# olm-flora-sqw-long.net
KiCad netlist of a schematic drawn in EAGLE
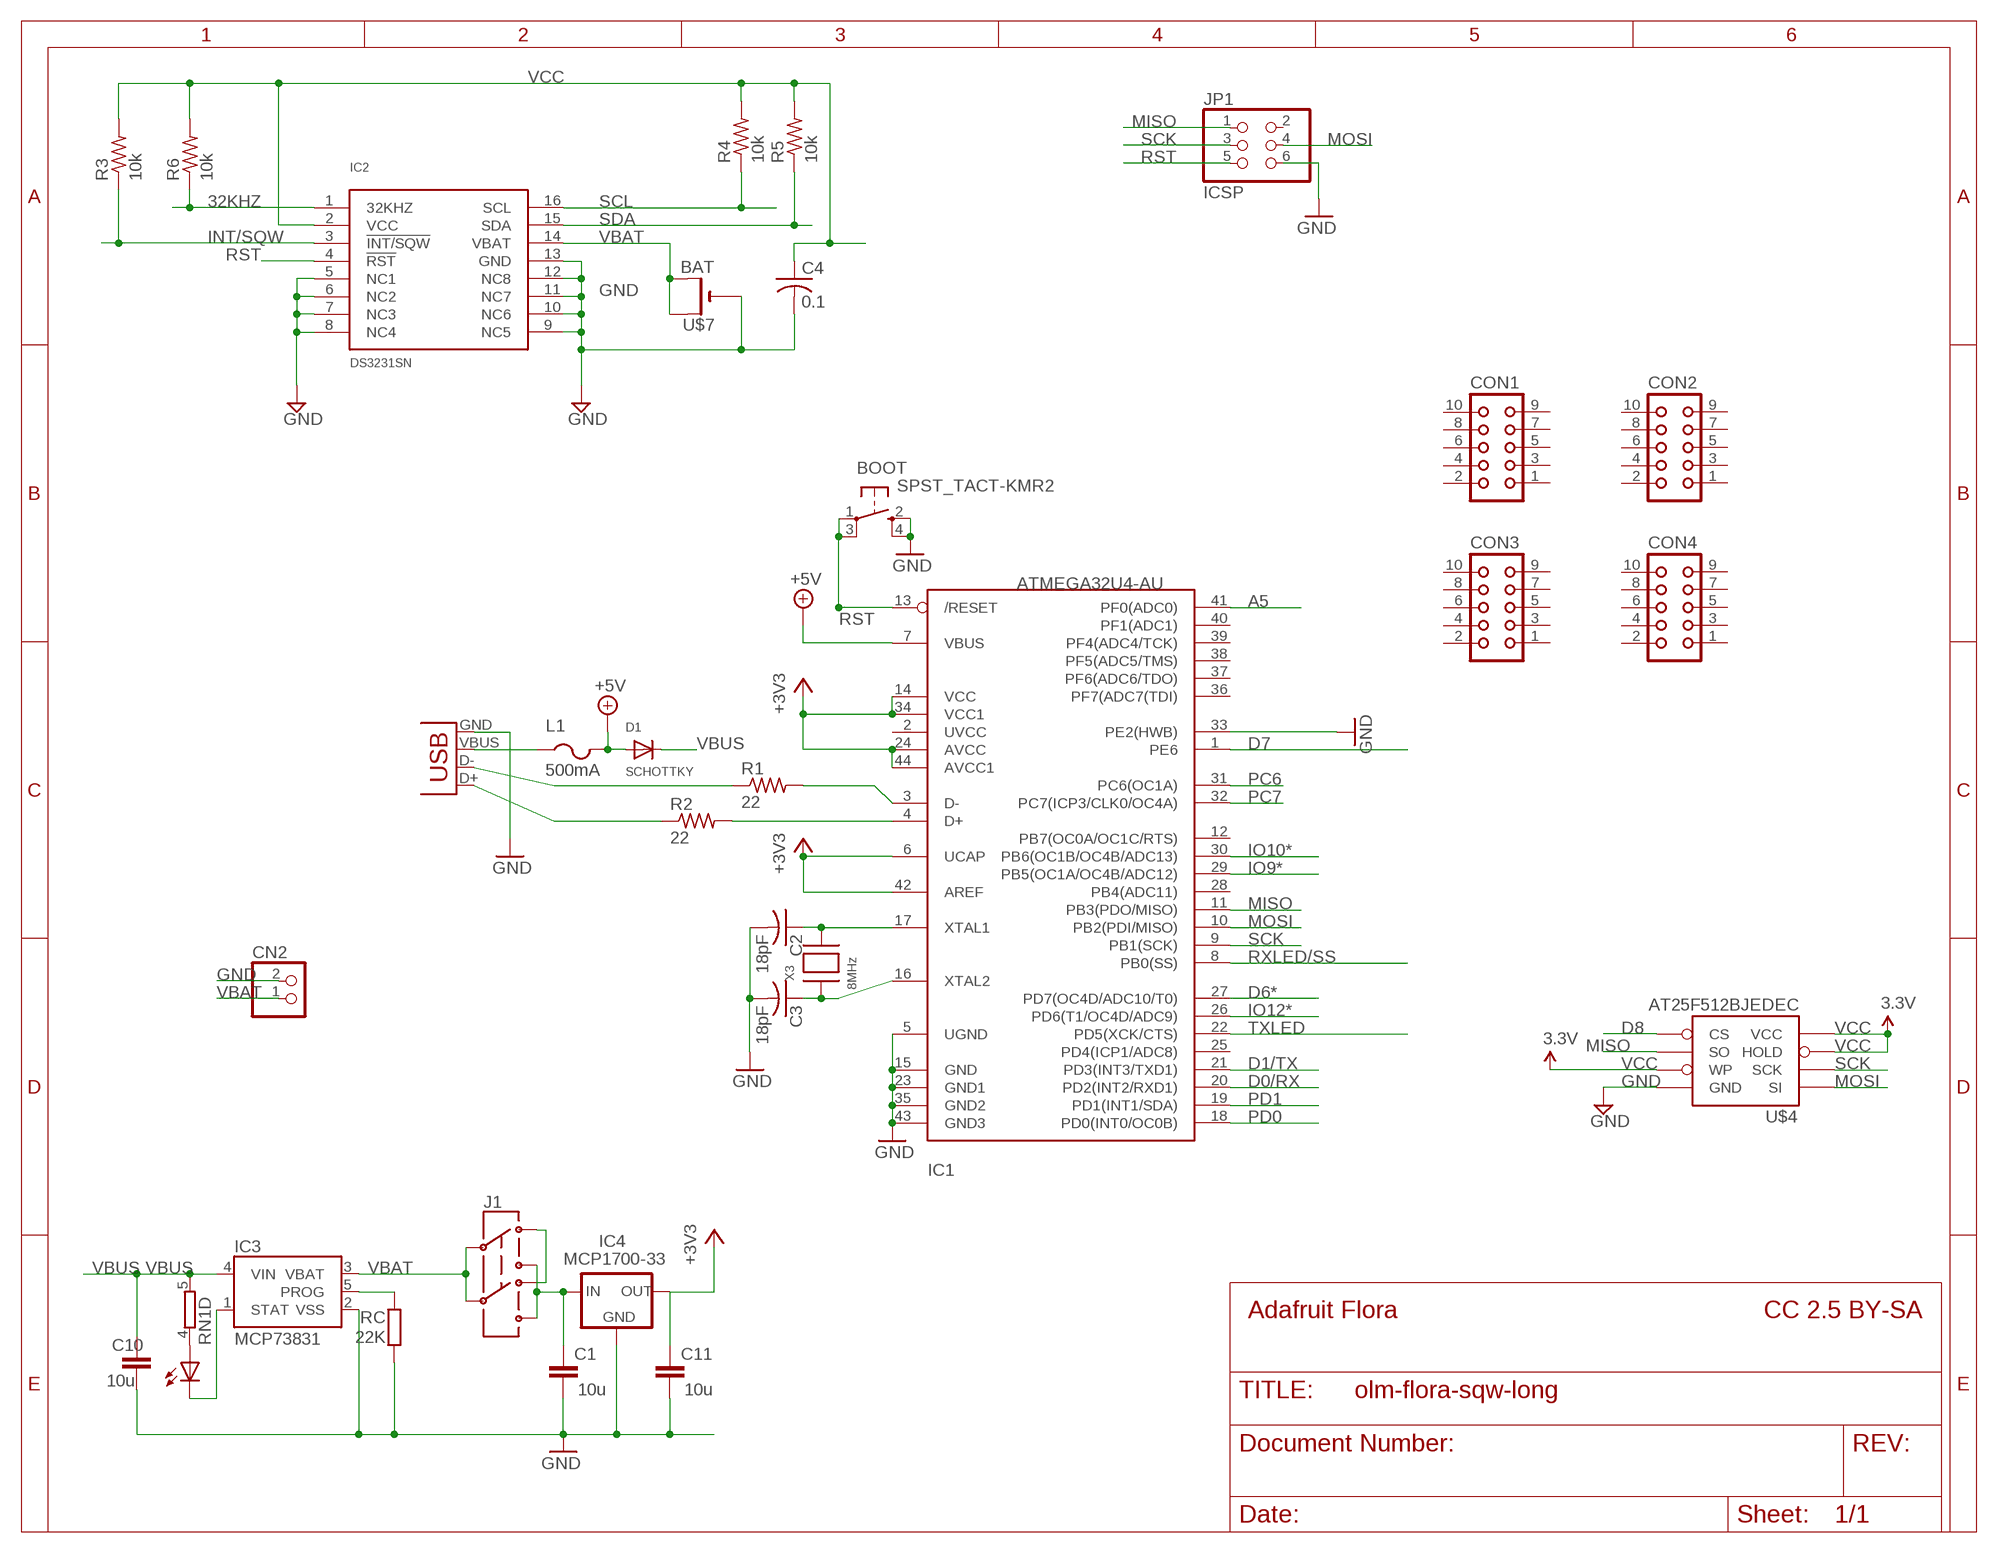
[diagram p0: schematic, sheet 1]

(export (version "E")
  (design (tool "Eeschema 10.0.6"))
  (components
    (comp (ref "BOOT")
      (value "SPST_TACT-KMR2")
      (footprint "eagle-import:KMR2")
      (libsource (lib "eagle-import") (part "SPST_TACT-KMR2"))
    )
    (comp (ref "C1")
      (value "10u")
      (footprint "eagle-import:C0805")
      (libsource (lib "eagle-import") (part "C-EUC0805"))
    )
    (comp (ref "C2")
      (value "18pF")
      (footprint "eagle-import:C0805K")
      (libsource (lib "eagle-import") (part "C-USC0805K"))
    )
    (comp (ref "C3")
      (value "18pF")
      (footprint "eagle-import:C0805K")
      (libsource (lib "eagle-import") (part "C-USC0805K"))
    )
    (comp (ref "C4")
      (value "0.1")
      (footprint "eagle-import:C0805K")
      (libsource (lib "eagle-import") (part "C-USC0805K"))
    )
    (comp (ref "C10")
      (value "10u")
      (footprint "eagle-import:C0805")
      (libsource (lib "eagle-import") (part "C-EUC0805"))
    )
    (comp (ref "C11")
      (value "10u")
      (footprint "eagle-import:C0805")
      (libsource (lib "eagle-import") (part "C-EUC0805"))
    )
    (comp (ref "CHG")
      (value "0805")
      (footprint "eagle-import:CHIPLED_0805")
      (libsource (lib "eagle-import") (part "LEDCHIPLED_0805"))
    )
    (comp (ref "CN2")
      (value "JST_2PIN-SMT-RA")
      (footprint "eagle-import:JST-PH-2-SMT-RA")
      (libsource (lib "eagle-import") (part "JST_2PIN-SMT-RA"))
    )
    (comp (ref "CON1")
      (value "CON10")
      (footprint "eagle-import:CON10")
      (libsource (lib "eagle-import") (part "CON10"))
    )
    (comp (ref "CON2")
      (value "CON10")
      (footprint "eagle-import:CON10")
      (libsource (lib "eagle-import") (part "CON10"))
    )
    (comp (ref "CON3")
      (value "CON10")
      (footprint "eagle-import:CON10")
      (libsource (lib "eagle-import") (part "CON10"))
    )
    (comp (ref "CON4")
      (value "CON10")
      (footprint "eagle-import:CON10")
      (libsource (lib "eagle-import") (part "CON10"))
    )
    (comp (ref "D1")
      (value "SCHOTTKY")
      (footprint "eagle-import:SOD-123")
      (libsource (lib "eagle-import") (part "DIODESOD-123"))
    )
    (comp (ref "IC1")
      (value "ATMEGA32U4-AU")
      (footprint "eagle-import:TQFP44")
      (libsource (lib "eagle-import") (part "ATMEGA32U4-AU"))
    )
    (comp (ref "IC2")
      (value "DS3231SN")
      (footprint "eagle-import:SO16W")
      (libsource (lib "eagle-import") (part "DS3231SN"))
    )
    (comp (ref "IC3")
      (value "MCP73831")
      (footprint "eagle-import:SOT23-5")
      (libsource (lib "eagle-import") (part "MCP73831"))
    )
    (comp (ref "IC4")
      (value "MCP1700-33")
      (footprint "eagle-import:SOT23")
      (libsource (lib "eagle-import") (part "MCP1700SOT233"))
    )
    (comp (ref "J1")
      (value "AYZ0202")
      (footprint "eagle-import:AYZ0202")
      (libsource (lib "eagle-import") (part "AYZ0202"))
    )
    (comp (ref "JP1")
      (value "ICSP")
      (footprint "eagle-import:2X03")
      (libsource (lib "eagle-import") (part "PINHD-2X3"))
    )
    (comp (ref "L1")
      (value "500mA")
      (footprint "eagle-import:R1206")
      (libsource (lib "eagle-import") (part "PTCFUSE-1206"))
    )
    (comp (ref "R1")
      (value "22")
      (footprint "eagle-import:R0805")
      (libsource (lib "eagle-import") (part "R-US_R0805"))
    )
    (comp (ref "R2")
      (value "22")
      (footprint "eagle-import:R0805")
      (libsource (lib "eagle-import") (part "R-US_R0805"))
    )
    (comp (ref "R3")
      (value "10k")
      (footprint "eagle-import:R0805")
      (libsource (lib "eagle-import") (part "R-US_R0805"))
    )
    (comp (ref "R4")
      (value "10k")
      (footprint "eagle-import:R0805")
      (libsource (lib "eagle-import") (part "R-US_R0805"))
    )
    (comp (ref "R5")
      (value "10k")
      (footprint "eagle-import:R0805")
      (libsource (lib "eagle-import") (part "R-US_R0805"))
    )
    (comp (ref "R6")
      (value "10k")
      (footprint "eagle-import:R0805")
      (libsource (lib "eagle-import") (part "R-US_R0805"))
    )
    (comp (ref "RC")
      (value "22K")
      (footprint "eagle-import:R0805")
      (libsource (lib "eagle-import") (part "R-EU_R0805"))
    )
    (comp (ref "RN1")
      (value "4R-NEXB38V")
      (footprint "eagle-import:EXB38V")
      (libsource (lib "eagle-import") (part "4R-NEXB38V"))
    )
    (comp (ref "U$4")
      (value "AT25F512BJEDEC")
      (footprint "eagle-import:SO08")
      (libsource (lib "eagle-import") (part "AT25F512BJEDEC"))
    )
    (comp (ref "U$7")
      (value "BAT")
      (footprint "eagle-import:CR1220-SMD")
      (libsource (lib "eagle-import") (part "CR1220SMT"))
    )
    (comp (ref "X1")
      (value "USBSMD")
      (footprint "eagle-import:USB-MINIB")
      (libsource (lib "eagle-import") (part "USBSMD"))
    )
    (comp (ref "X3")
      (value "8MHz")
      (footprint "eagle-import:NX5032")
      (libsource (lib "eagle-import") (part "XTALNX5032"))
    )
  )
  (nets
    (net (code "1") (name "+3V3") (class "Default")
      (node (ref "C11") (pin "1") (pinfunction "1_1") (pintype "passive"))
      (node (ref "IC1") (pin "14") (pinfunction "VCC_14") (pintype "bidirectional"))
      (node (ref "IC1") (pin "24") (pinfunction "AVCC_24") (pintype "bidirectional"))
      (node (ref "IC1") (pin "34") (pinfunction "VCC1_34") (pintype "bidirectional"))
      (node (ref "IC1") (pin "42") (pinfunction "AREF_42") (pintype "bidirectional"))
      (node (ref "IC1") (pin "44") (pinfunction "AVCC1_44") (pintype "bidirectional"))
      (node (ref "IC1") (pin "6") (pinfunction "UCAP_6") (pintype "bidirectional"))
      (node (ref "IC4") (pin "2") (pinfunction "OUT_2") (pintype "passive"))
    )
    (net (code "2") (name "+5V") (class "Default")
      (node (ref "D1") (pin "A") (pinfunction "A_A") (pintype "passive"))
      (node (ref "IC1") (pin "7") (pinfunction "VBUS_7") (pintype "bidirectional"))
      (node (ref "L1") (pin "2") (pinfunction "2_2") (pintype "passive"))
    )
    (net (code "3") (name "/32KHZ") (class "Default")
      (node (ref "IC2") (pin "1") (pinfunction "32KHZ_1") (pintype "bidirectional"))
      (node (ref "R6") (pin "1") (pinfunction "1_1") (pintype "passive"))
    )
    (net (code "4") (name "/A5") (class "Default")
      (node (ref "IC1") (pin "41") (pinfunction "PF0(ADC0)_41") (pintype "bidirectional"))
    )
    (net (code "5") (name "/D0{slash}RX") (class "Default")
      (node (ref "IC1") (pin "20") (pinfunction "PD2(INT2/RXD1)_20") (pintype "bidirectional"))
    )
    (net (code "6") (name "/D1{slash}TX") (class "Default")
      (node (ref "IC1") (pin "21") (pinfunction "PD3(INT3/TXD1)_21") (pintype "bidirectional"))
    )
    (net (code "7") (name "/D6*") (class "Default")
      (node (ref "IC1") (pin "27") (pinfunction "PD7(OC4D/ADC10/T0)_27") (pintype "bidirectional"))
    )
    (net (code "8") (name "/D7") (class "Default")
      (node (ref "IC1") (pin "1") (pinfunction "PE6_1") (pintype "bidirectional"))
    )
    (net (code "9") (name "/D8") (class "Default")
      (node (ref "U$4") (pin "1_CS") (pinfunction "CS_1_CS") (pintype "bidirectional"))
    )
    (net (code "10") (name "/INT{slash}SQW") (class "Default")
      (node (ref "IC2") (pin "3") (pinfunction "~{INT/SQW}_3") (pintype "bidirectional"))
      (node (ref "R3") (pin "1") (pinfunction "1_1") (pintype "passive"))
    )
    (net (code "11") (name "/IO9*") (class "Default")
      (node (ref "IC1") (pin "29") (pinfunction "PB5(OC1A/OC4B/ADC12)_29") (pintype "bidirectional"))
    )
    (net (code "12") (name "/IO10*") (class "Default")
      (node (ref "IC1") (pin "30") (pinfunction "PB6(OC1B/OC4B/ADC13)_30") (pintype "bidirectional"))
    )
    (net (code "13") (name "/IO12*") (class "Default")
      (node (ref "IC1") (pin "26") (pinfunction "PD6(T1/OC4D/ADC9)_26") (pintype "bidirectional"))
    )
    (net (code "14") (name "/MISO") (class "Default")
      (node (ref "IC1") (pin "11") (pinfunction "PB3(PDO/MISO)_11") (pintype "bidirectional"))
      (node (ref "JP1") (pin "1") (pinfunction "1_1") (pintype "passive"))
      (node (ref "U$4") (pin "2_SO") (pinfunction "SO_2_SO") (pintype "bidirectional"))
    )
    (net (code "15") (name "/MOSI") (class "Default")
      (node (ref "IC1") (pin "10") (pinfunction "PB2(PDI/MISO)_10") (pintype "bidirectional"))
      (node (ref "JP1") (pin "4") (pinfunction "4_4") (pintype "passive"))
      (node (ref "U$4") (pin "5_SI") (pinfunction "SI_5_SI") (pintype "bidirectional"))
    )
    (net (code "16") (name "/PC6") (class "Default")
      (node (ref "IC1") (pin "31") (pinfunction "PC6(OC1A)_31") (pintype "bidirectional"))
    )
    (net (code "17") (name "/PC7") (class "Default")
      (node (ref "IC1") (pin "32") (pinfunction "PC7(ICP3/CLK0/OC4A)_32") (pintype "bidirectional"))
    )
    (net (code "18") (name "/PD0") (class "Default")
      (node (ref "IC1") (pin "18") (pinfunction "PD0(INT0/OC0B)_18") (pintype "bidirectional"))
    )
    (net (code "19") (name "/PD1") (class "Default")
      (node (ref "IC1") (pin "19") (pinfunction "PD1(INT1/SDA)_19") (pintype "bidirectional"))
    )
    (net (code "20") (name "/RST") (class "Default")
      (node (ref "BOOT") (pin "1") (pinfunction "P_1") (pintype "passive"))
      (node (ref "BOOT") (pin "3") (pinfunction "P1_3") (pintype "passive"))
      (node (ref "IC1") (pin "13") (pinfunction "/RESET_13") (pintype "bidirectional"))
      (node (ref "IC2") (pin "4") (pinfunction "~{RST}_4") (pintype "bidirectional"))
      (node (ref "JP1") (pin "5") (pinfunction "5_5") (pintype "passive"))
    )
    (net (code "21") (name "/RXLED{slash}SS") (class "Default")
      (node (ref "IC1") (pin "8") (pinfunction "PB0(SS)_8") (pintype "bidirectional"))
    )
    (net (code "22") (name "/SCK") (class "Default")
      (node (ref "IC1") (pin "9") (pinfunction "PB1(SCK)_9") (pintype "bidirectional"))
      (node (ref "JP1") (pin "3") (pinfunction "3_3") (pintype "passive"))
      (node (ref "U$4") (pin "6_SCK") (pinfunction "SCK_6_SCK") (pintype "bidirectional"))
    )
    (net (code "23") (name "/SCL") (class "Default")
      (node (ref "IC2") (pin "16") (pinfunction "SCL_16") (pintype "bidirectional"))
      (node (ref "R4") (pin "1") (pinfunction "1_1") (pintype "passive"))
    )
    (net (code "24") (name "/SDA") (class "Default")
      (node (ref "IC2") (pin "15") (pinfunction "SDA_15") (pintype "bidirectional"))
      (node (ref "R5") (pin "1") (pinfunction "1_1") (pintype "passive"))
    )
    (net (code "25") (name "/TXLED") (class "Default")
      (node (ref "IC1") (pin "22") (pinfunction "PD5(XCK/CTS)_22") (pintype "bidirectional"))
    )
    (net (code "26") (name "/VBAT") (class "Default")
      (node (ref "CN2") (pin "1") (pinfunction "2_1") (pintype "passive"))
      (node (ref "IC2") (pin "14") (pinfunction "VBAT_14") (pintype "bidirectional"))
      (node (ref "IC3") (pin "3") (pinfunction "VBAT_3") (pintype "power_in"))
      (node (ref "J1") (pin "2") (pinfunction "2_2") (pintype "bidirectional"))
      (node (ref "J1") (pin "5") (pinfunction "5_5") (pintype "bidirectional"))
      (node (ref "U$7") (pin "+$1") (pinfunction "+_+$1") (pintype "passive"))
      (node (ref "U$7") (pin "+$2") (pinfunction "+1_+$2") (pintype "passive"))
    )
    (net (code "27") (name "/VBUS") (class "Default")
      (node (ref "C10") (pin "1") (pinfunction "1_1") (pintype "passive"))
      (node (ref "D1") (pin "C") (pinfunction "C_C") (pintype "passive"))
      (node (ref "IC3") (pin "4") (pinfunction "VIN_4") (pintype "power_in"))
      (node (ref "L1") (pin "1") (pinfunction "1_1") (pintype "passive"))
      (node (ref "RN1") (pin "5") (pinfunction "2_5") (pintype "passive"))
      (node (ref "X1") (pin "VBUS") (pinfunction "VBUS_VBUS") (pintype "bidirectional"))
    )
    (net (code "28") (name "3.3V") (class "Default")
      (node (ref "C4") (pin "1") (pinfunction "1_1") (pintype "passive"))
      (node (ref "IC2") (pin "2") (pinfunction "VCC_2") (pintype "bidirectional"))
      (node (ref "R3") (pin "2") (pinfunction "2_2") (pintype "passive"))
      (node (ref "R4") (pin "2") (pinfunction "2_2") (pintype "passive"))
      (node (ref "R5") (pin "2") (pinfunction "2_2") (pintype "passive"))
      (node (ref "R6") (pin "2") (pinfunction "2_2") (pintype "passive"))
      (node (ref "U$4") (pin "3_WP") (pinfunction "WP_3_WP") (pintype "bidirectional"))
      (node (ref "U$4") (pin "7_HOLD") (pinfunction "HOLD_7_HOLD") (pintype "bidirectional"))
      (node (ref "U$4") (pin "8_VCC") (pinfunction "VCC_8_VCC") (pintype "bidirectional"))
    )
    (net (code "29") (name "GND") (class "Default")
      (node (ref "BOOT") (pin "2") (pinfunction "S_2") (pintype "passive"))
      (node (ref "BOOT") (pin "4") (pinfunction "S1_4") (pintype "passive"))
      (node (ref "C1") (pin "2") (pinfunction "2_2") (pintype "passive"))
      (node (ref "C10") (pin "2") (pinfunction "2_2") (pintype "passive"))
      (node (ref "C11") (pin "2") (pinfunction "2_2") (pintype "passive"))
      (node (ref "C2") (pin "2") (pinfunction "2_2") (pintype "passive"))
      (node (ref "C3") (pin "2") (pinfunction "2_2") (pintype "passive"))
      (node (ref "C4") (pin "2") (pinfunction "2_2") (pintype "passive"))
      (node (ref "CN2") (pin "2") (pinfunction "1_2") (pintype "passive"))
      (node (ref "IC1") (pin "15") (pinfunction "GND_15") (pintype "bidirectional"))
      (node (ref "IC1") (pin "23") (pinfunction "GND1_23") (pintype "bidirectional"))
      (node (ref "IC1") (pin "33") (pinfunction "PE2(HWB)_33") (pintype "bidirectional"))
      (node (ref "IC1") (pin "35") (pinfunction "GND2_35") (pintype "bidirectional"))
      (node (ref "IC1") (pin "43") (pinfunction "GND3_43") (pintype "bidirectional"))
      (node (ref "IC1") (pin "5") (pinfunction "UGND_5") (pintype "bidirectional"))
      (node (ref "IC2") (pin "10") (pinfunction "NC6_10") (pintype "bidirectional"))
      (node (ref "IC2") (pin "11") (pinfunction "NC7_11") (pintype "bidirectional"))
      (node (ref "IC2") (pin "12") (pinfunction "NC8_12") (pintype "bidirectional"))
      (node (ref "IC2") (pin "13") (pinfunction "GND_13") (pintype "bidirectional"))
      (node (ref "IC2") (pin "5") (pinfunction "NC1_5") (pintype "bidirectional"))
      (node (ref "IC2") (pin "6") (pinfunction "NC2_6") (pintype "bidirectional"))
      (node (ref "IC2") (pin "7") (pinfunction "NC3_7") (pintype "bidirectional"))
      (node (ref "IC2") (pin "8") (pinfunction "NC4_8") (pintype "bidirectional"))
      (node (ref "IC2") (pin "9") (pinfunction "NC5_9") (pintype "bidirectional"))
      (node (ref "IC3") (pin "2") (pinfunction "VSS_2") (pintype "power_in"))
      (node (ref "IC4") (pin "1") (pinfunction "GND_1") (pintype "input"))
      (node (ref "JP1") (pin "6") (pinfunction "6_6") (pintype "passive"))
      (node (ref "RC") (pin "1") (pinfunction "1_1") (pintype "passive"))
      (node (ref "U$4") (pin "4_GND") (pinfunction "GND_4_GND") (pintype "bidirectional"))
      (node (ref "U$7") (pin "-") (pinfunction "-_-") (pintype "passive"))
      (node (ref "X1") (pin "GND") (pinfunction "GND_GND") (pintype "bidirectional"))
    )
    (net (code "30") (name "Net-(IC1-D+)") (class "Default")
      (node (ref "IC1") (pin "4") (pinfunction "D+_4") (pintype "bidirectional"))
      (node (ref "R2") (pin "2") (pinfunction "2_2") (pintype "passive"))
    )
    (net (code "31") (name "Net-(IC1-D-)") (class "Default")
      (node (ref "IC1") (pin "3") (pinfunction "D-_3") (pintype "bidirectional"))
      (node (ref "R1") (pin "2") (pinfunction "2_2") (pintype "passive"))
    )
    (net (code "32") (name "Net-(IC1-XTAL1)") (class "Default")
      (node (ref "C2") (pin "1") (pinfunction "1_1") (pintype "passive"))
      (node (ref "IC1") (pin "17") (pinfunction "XTAL1_17") (pintype "bidirectional"))
      (node (ref "X3") (pin "P$2") (pinfunction "P$2_P$2") (pintype "bidirectional"))
    )
    (net (code "33") (name "Net-(IC1-XTAL2)") (class "Default")
      (node (ref "C3") (pin "1") (pinfunction "1_1") (pintype "passive"))
      (node (ref "IC1") (pin "16") (pinfunction "XTAL2_16") (pintype "bidirectional"))
      (node (ref "X3") (pin "P$1") (pinfunction "P$1_P$1") (pintype "bidirectional"))
    )
    (net (code "34") (name "Net-(IC3-PROG)") (class "Default")
      (node (ref "IC3") (pin "5") (pinfunction "PROG_5") (pintype "input"))
      (node (ref "RC") (pin "2") (pinfunction "2_2") (pintype "passive"))
    )
    (net (code "35") (name "Net-(IC3-STAT)") (class "Default")
      (node (ref "CHG") (pin "C") (pinfunction "C_C") (pintype "passive"))
      (node (ref "IC3") (pin "1") (pinfunction "STAT_1") (pintype "output"))
    )
    (net (code "36") (name "Net-(IC4-IN)") (class "Default")
      (node (ref "C1") (pin "1") (pinfunction "1_1") (pintype "passive"))
      (node (ref "IC4") (pin "3") (pinfunction "IN_3") (pintype "input"))
      (node (ref "J1") (pin "1") (pinfunction "3_1") (pintype "bidirectional"))
      (node (ref "J1") (pin "4") (pinfunction "6_4") (pintype "bidirectional"))
    )
    (net (code "37") (name "Net-(J1-1)") (class "Default")
      (node (ref "J1") (pin "3") (pinfunction "1_3") (pintype "bidirectional"))
      (node (ref "J1") (pin "6") (pinfunction "4_6") (pintype "bidirectional"))
    )
    (net (code "38") (name "Net-(R1-Pad1)") (class "Default")
      (node (ref "R1") (pin "1") (pinfunction "1_1") (pintype "passive"))
      (node (ref "X1") (pin "D-") (pinfunction "D-_D-") (pintype "bidirectional"))
    )
    (net (code "39") (name "Net-(R2-Pad1)") (class "Default")
      (node (ref "R2") (pin "1") (pinfunction "1_1") (pintype "passive"))
      (node (ref "X1") (pin "D+") (pinfunction "D+_D+") (pintype "bidirectional"))
    )
    (net (code "40") (name "Net-(RN1D-1)") (class "Default")
      (node (ref "CHG") (pin "A") (pinfunction "A_A") (pintype "passive"))
      (node (ref "RN1") (pin "4") (pinfunction "1_4") (pintype "passive"))
    )
    (net (code "41") (name "unconnected-(CON1-Pad1)") (class "Default")
      (node (ref "CON1") (pin "1") (pinfunction "1_1") (pintype "passive"))
    )
    (net (code "42") (name "unconnected-(CON1-Pad2)") (class "Default")
      (node (ref "CON1") (pin "2") (pinfunction "2_2") (pintype "passive"))
    )
    (net (code "43") (name "unconnected-(CON1-Pad3)") (class "Default")
      (node (ref "CON1") (pin "3") (pinfunction "3_3") (pintype "passive"))
    )
    (net (code "44") (name "unconnected-(CON1-Pad4)") (class "Default")
      (node (ref "CON1") (pin "4") (pinfunction "4_4") (pintype "passive"))
    )
    (net (code "45") (name "unconnected-(CON1-Pad5)") (class "Default")
      (node (ref "CON1") (pin "5") (pinfunction "5_5") (pintype "passive"))
    )
    (net (code "46") (name "unconnected-(CON1-Pad6)") (class "Default")
      (node (ref "CON1") (pin "6") (pinfunction "6_6") (pintype "passive"))
    )
    (net (code "47") (name "unconnected-(CON1-Pad7)") (class "Default")
      (node (ref "CON1") (pin "7") (pinfunction "7_7") (pintype "passive"))
    )
    (net (code "48") (name "unconnected-(CON1-Pad8)") (class "Default")
      (node (ref "CON1") (pin "8") (pinfunction "8_8") (pintype "passive"))
    )
    (net (code "49") (name "unconnected-(CON1-Pad9)") (class "Default")
      (node (ref "CON1") (pin "9") (pinfunction "9_9") (pintype "passive"))
    )
    (net (code "50") (name "unconnected-(CON1-Pad10)") (class "Default")
      (node (ref "CON1") (pin "10") (pinfunction "10_10") (pintype "passive"))
    )
    (net (code "51") (name "unconnected-(CON2-Pad1)") (class "Default")
      (node (ref "CON2") (pin "1") (pinfunction "1_1") (pintype "passive"))
    )
    (net (code "52") (name "unconnected-(CON2-Pad2)") (class "Default")
      (node (ref "CON2") (pin "2") (pinfunction "2_2") (pintype "passive"))
    )
    (net (code "53") (name "unconnected-(CON2-Pad3)") (class "Default")
      (node (ref "CON2") (pin "3") (pinfunction "3_3") (pintype "passive"))
    )
    (net (code "54") (name "unconnected-(CON2-Pad4)") (class "Default")
      (node (ref "CON2") (pin "4") (pinfunction "4_4") (pintype "passive"))
    )
    (net (code "55") (name "unconnected-(CON2-Pad5)") (class "Default")
      (node (ref "CON2") (pin "5") (pinfunction "5_5") (pintype "passive"))
    )
    (net (code "56") (name "unconnected-(CON2-Pad6)") (class "Default")
      (node (ref "CON2") (pin "6") (pinfunction "6_6") (pintype "passive"))
    )
    (net (code "57") (name "unconnected-(CON2-Pad7)") (class "Default")
      (node (ref "CON2") (pin "7") (pinfunction "7_7") (pintype "passive"))
    )
    (net (code "58") (name "unconnected-(CON2-Pad8)") (class "Default")
      (node (ref "CON2") (pin "8") (pinfunction "8_8") (pintype "passive"))
    )
    (net (code "59") (name "unconnected-(CON2-Pad9)") (class "Default")
      (node (ref "CON2") (pin "9") (pinfunction "9_9") (pintype "passive"))
    )
    (net (code "60") (name "unconnected-(CON2-Pad10)") (class "Default")
      (node (ref "CON2") (pin "10") (pinfunction "10_10") (pintype "passive"))
    )
    (net (code "61") (name "unconnected-(CON3-Pad1)") (class "Default")
      (node (ref "CON3") (pin "1") (pinfunction "1_1") (pintype "passive"))
    )
    (net (code "62") (name "unconnected-(CON3-Pad2)") (class "Default")
      (node (ref "CON3") (pin "2") (pinfunction "2_2") (pintype "passive"))
    )
    (net (code "63") (name "unconnected-(CON3-Pad3)") (class "Default")
      (node (ref "CON3") (pin "3") (pinfunction "3_3") (pintype "passive"))
    )
    (net (code "64") (name "unconnected-(CON3-Pad4)") (class "Default")
      (node (ref "CON3") (pin "4") (pinfunction "4_4") (pintype "passive"))
    )
    (net (code "65") (name "unconnected-(CON3-Pad5)") (class "Default")
      (node (ref "CON3") (pin "5") (pinfunction "5_5") (pintype "passive"))
    )
    (net (code "66") (name "unconnected-(CON3-Pad6)") (class "Default")
      (node (ref "CON3") (pin "6") (pinfunction "6_6") (pintype "passive"))
    )
    (net (code "67") (name "unconnected-(CON3-Pad7)") (class "Default")
      (node (ref "CON3") (pin "7") (pinfunction "7_7") (pintype "passive"))
    )
    (net (code "68") (name "unconnected-(CON3-Pad8)") (class "Default")
      (node (ref "CON3") (pin "8") (pinfunction "8_8") (pintype "passive"))
    )
    (net (code "69") (name "unconnected-(CON3-Pad9)") (class "Default")
      (node (ref "CON3") (pin "9") (pinfunction "9_9") (pintype "passive"))
    )
    (net (code "70") (name "unconnected-(CON3-Pad10)") (class "Default")
      (node (ref "CON3") (pin "10") (pinfunction "10_10") (pintype "passive"))
    )
    (net (code "71") (name "unconnected-(CON4-Pad1)") (class "Default")
      (node (ref "CON4") (pin "1") (pinfunction "1_1") (pintype "passive"))
    )
    (net (code "72") (name "unconnected-(CON4-Pad2)") (class "Default")
      (node (ref "CON4") (pin "2") (pinfunction "2_2") (pintype "passive"))
    )
    (net (code "73") (name "unconnected-(CON4-Pad3)") (class "Default")
      (node (ref "CON4") (pin "3") (pinfunction "3_3") (pintype "passive"))
    )
    (net (code "74") (name "unconnected-(CON4-Pad4)") (class "Default")
      (node (ref "CON4") (pin "4") (pinfunction "4_4") (pintype "passive"))
    )
    (net (code "75") (name "unconnected-(CON4-Pad5)") (class "Default")
      (node (ref "CON4") (pin "5") (pinfunction "5_5") (pintype "passive"))
    )
    (net (code "76") (name "unconnected-(CON4-Pad6)") (class "Default")
      (node (ref "CON4") (pin "6") (pinfunction "6_6") (pintype "passive"))
    )
    (net (code "77") (name "unconnected-(CON4-Pad7)") (class "Default")
      (node (ref "CON4") (pin "7") (pinfunction "7_7") (pintype "passive"))
    )
    (net (code "78") (name "unconnected-(CON4-Pad8)") (class "Default")
      (node (ref "CON4") (pin "8") (pinfunction "8_8") (pintype "passive"))
    )
    (net (code "79") (name "unconnected-(CON4-Pad9)") (class "Default")
      (node (ref "CON4") (pin "9") (pinfunction "9_9") (pintype "passive"))
    )
    (net (code "80") (name "unconnected-(CON4-Pad10)") (class "Default")
      (node (ref "CON4") (pin "10") (pinfunction "10_10") (pintype "passive"))
    )
    (net (code "81") (name "unconnected-(IC1-PB4(ADC11)-Pad28)") (class "Default")
      (node (ref "IC1") (pin "28") (pinfunction "PB4(ADC11)_28") (pintype "bidirectional"))
    )
    (net (code "82") (name "unconnected-(IC1-PB7(OC0A{slash}OC1C{slash}RTS)-Pad12)") (class "Default")
      (node (ref "IC1") (pin "12") (pinfunction "PB7(OC0A/OC1C/RTS)_12") (pintype "bidirectional"))
    )
    (net (code "83") (name "unconnected-(IC1-PD4(ICP1{slash}ADC8)-Pad25)") (class "Default")
      (node (ref "IC1") (pin "25") (pinfunction "PD4(ICP1/ADC8)_25") (pintype "bidirectional"))
    )
    (net (code "84") (name "unconnected-(IC1-PF1(ADC1)-Pad40)") (class "Default")
      (node (ref "IC1") (pin "40") (pinfunction "PF1(ADC1)_40") (pintype "bidirectional"))
    )
    (net (code "85") (name "unconnected-(IC1-PF4(ADC4{slash}TCK)-Pad39)") (class "Default")
      (node (ref "IC1") (pin "39") (pinfunction "PF4(ADC4/TCK)_39") (pintype "bidirectional"))
    )
    (net (code "86") (name "unconnected-(IC1-PF5(ADC5{slash}TMS)-Pad38)") (class "Default")
      (node (ref "IC1") (pin "38") (pinfunction "PF5(ADC5/TMS)_38") (pintype "bidirectional"))
    )
    (net (code "87") (name "unconnected-(IC1-PF6(ADC6{slash}TDO)-Pad37)") (class "Default")
      (node (ref "IC1") (pin "37") (pinfunction "PF6(ADC6/TDO)_37") (pintype "bidirectional"))
    )
    (net (code "88") (name "unconnected-(IC1-PF7(ADC7(TDI)-Pad36)") (class "Default")
      (node (ref "IC1") (pin "36") (pinfunction "PF7(ADC7(TDI)_36") (pintype "bidirectional"))
    )
    (net (code "89") (name "unconnected-(IC1-UVCC-Pad2)") (class "Default")
      (node (ref "IC1") (pin "2") (pinfunction "UVCC_2") (pintype "bidirectional"))
    )
    (net (code "90") (name "unconnected-(JP1-Pad2)") (class "Default")
      (node (ref "JP1") (pin "2") (pinfunction "2_2") (pintype "passive"))
    )
  )
)
